# Sheet1.net
KiCad netlist of a schematic drawn in Altium Designer
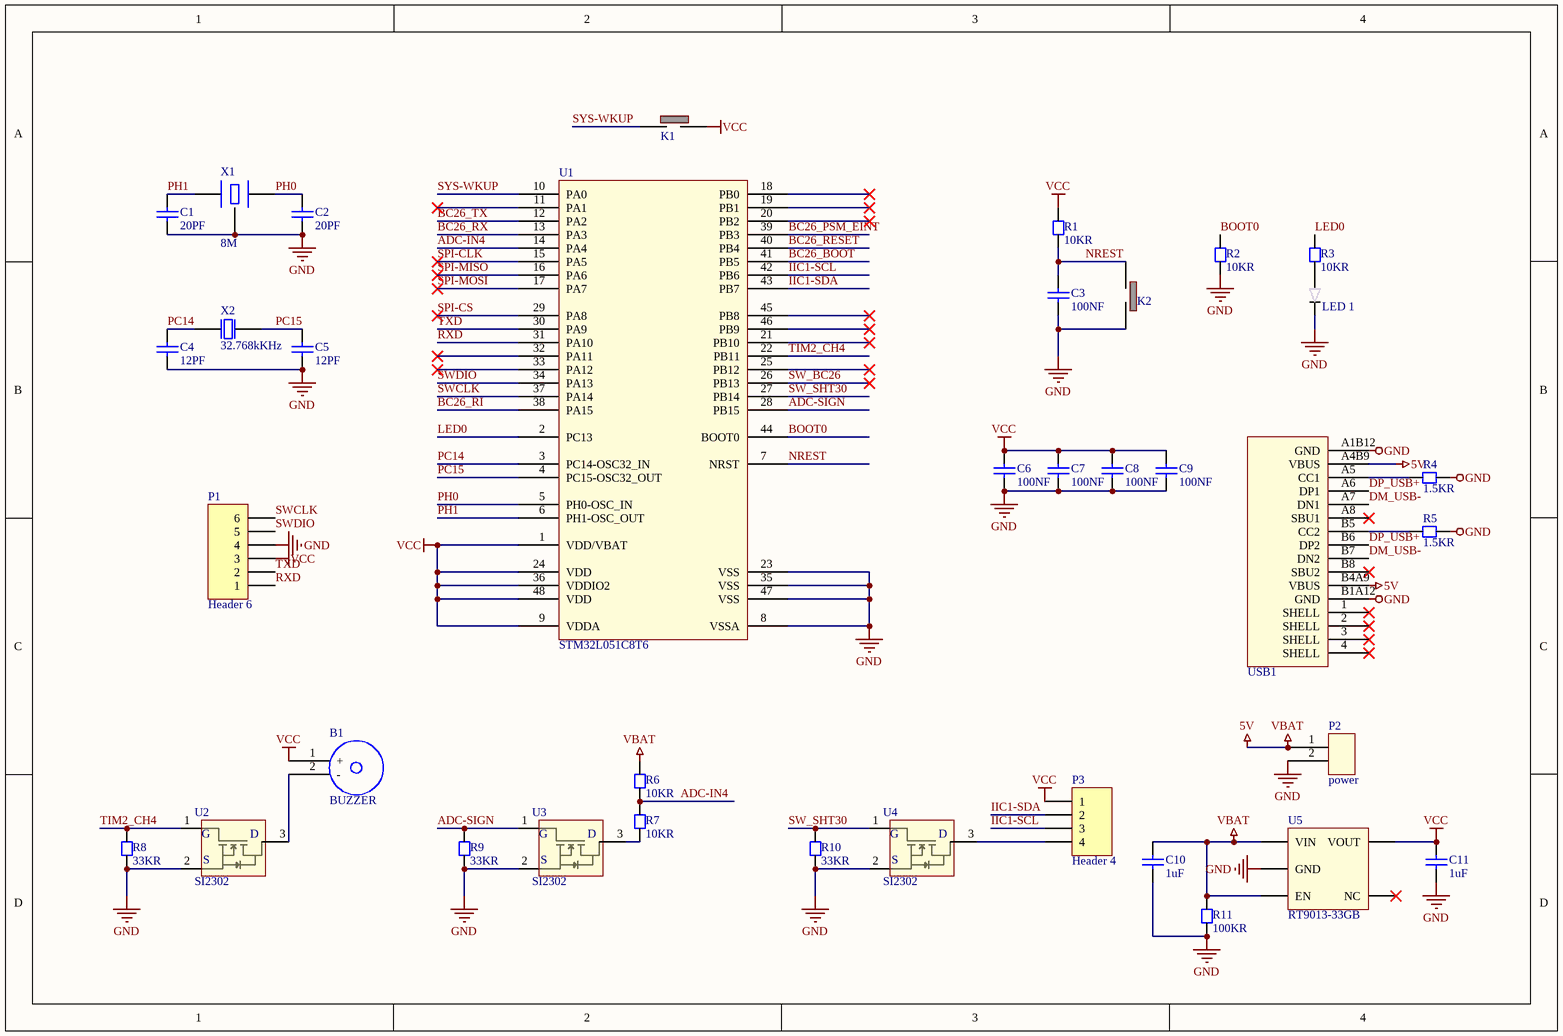
[diagram p0: Sheet1.SchDoc]

(export (version "E")
  (design (tool "Eeschema 10.0.6"))
  (components
    (comp (ref "B1")
      (value "BUZZER")
      (footprint "Buzzer")
      (description "蜂鸣器 0905 直径9毫米，高度5毫米")
      (libsource (lib "tianxiaohua_Schlib") (part "BUZZER"))
    )
    (comp (ref "C1")
      (value "20PF")
      (footprint "CC1608-0603")
      (description "贴片电容")
      (libsource (lib "tianxiaohua_Schlib") (part "Chip capacitor"))
    )
    (comp (ref "C2")
      (value "20PF")
      (footprint "CC1608-0603")
      (description "贴片电容")
      (libsource (lib "tianxiaohua_Schlib") (part "Chip capacitor"))
    )
    (comp (ref "C3")
      (value "100NF")
      (footprint "CC1608-0603")
      (description "贴片电容")
      (libsource (lib "tianxiaohua_Schlib") (part "Chip capacitor"))
    )
    (comp (ref "C4")
      (value "12PF")
      (footprint "CC1608-0603")
      (description "贴片电容")
      (libsource (lib "tianxiaohua_Schlib") (part "Chip capacitor"))
    )
    (comp (ref "C5")
      (value "12PF")
      (footprint "CC1608-0603")
      (description "贴片电容")
      (libsource (lib "tianxiaohua_Schlib") (part "Chip capacitor"))
    )
    (comp (ref "C6")
      (value "100NF")
      (footprint "CC1608-0603")
      (description "贴片电容")
      (libsource (lib "tianxiaohua_Schlib") (part "Chip capacitor"))
    )
    (comp (ref "C7")
      (value "100NF")
      (footprint "CC1608-0603")
      (description "贴片电容")
      (libsource (lib "tianxiaohua_Schlib") (part "Chip capacitor"))
    )
    (comp (ref "C8")
      (value "100NF")
      (footprint "CC1608-0603")
      (description "贴片电容")
      (libsource (lib "tianxiaohua_Schlib") (part "Chip capacitor"))
    )
    (comp (ref "C9")
      (value "100NF")
      (footprint "CC1608-0603")
      (description "贴片电容")
      (libsource (lib "tianxiaohua_Schlib") (part "Chip capacitor"))
    )
    (comp (ref "C10")
      (value "1uF")
      (footprint "CC1608-0603")
      (description "贴片电容")
      (libsource (lib "tianxiaohua_Schlib") (part "Chip capacitor"))
    )
    (comp (ref "C11")
      (value "1uF")
      (footprint "CC1608-0603")
      (description "贴片电容")
      (libsource (lib "tianxiaohua_Schlib") (part "Chip capacitor"))
    )
    (comp (ref "K1")
      (value "KEY 3*4")
      (footprint "KEY 3*4")
      (description "轻触开关按键")
      (libsource (lib "tianxiaohua_Schlib") (part "KEY 3*4"))
    )
    (comp (ref "K2")
      (value "KEY 3*4")
      (footprint "KEY 3*4")
      (description "轻触开关按键")
      (libsource (lib "") (part "KEY 3*4_1"))
    )
    (comp (ref "LED 1")
      (value "LED 0603")
      (footprint "LED 0603")
      (libsource (lib "tianxiaohua_Schlib") (part "LED 0603"))
    )
    (comp (ref "P1")
      (value "Header 6")
      (footprint "HDR1X6")
      (description "Header, 6-Pin")
      (fields (field (name "PUBLISHER") "Altium Limited"))
      (libsource (lib "EButterflyIntegratedLibrary") (part "Header 6"))
    )
    (comp (ref "P2")
      (value "power")
      (footprint "power-5V")
      (libsource (lib "tianxiaohua_Schlib") (part "power"))
    )
    (comp (ref "P3")
      (value "Header 4")
      (footprint "HX2.54-4")
      (description "Header, 4-Pin")
      (fields (field (name "PUBLISHER") "Altium Limited"))
      (libsource (lib "EButterflyIntegratedLibrary") (part "Header 4"))
    )
    (comp (ref "R1")
      (value "10KR")
      (footprint "CR1608-0603")
      (description "贴片电阻")
      (libsource (lib "tianxiaohua_Schlib") (part "Chip resistor"))
    )
    (comp (ref "R2")
      (value "10KR")
      (footprint "CR1608-0603")
      (description "贴片电阻")
      (libsource (lib "tianxiaohua_Schlib") (part "Chip resistor"))
    )
    (comp (ref "R3")
      (value "10KR")
      (footprint "CR1608-0603")
      (description "贴片电阻")
      (libsource (lib "tianxiaohua_Schlib") (part "Chip resistor"))
    )
    (comp (ref "R4")
      (value "1.5KR")
      (footprint "CR1608-0603")
      (description "贴片电阻")
      (libsource (lib "") (part "Chip resistor_2"))
    )
    (comp (ref "R5")
      (value "1.5KR")
      (footprint "CR1608-0603")
      (description "贴片电阻")
      (libsource (lib "") (part "Chip resistor_2"))
    )
    (comp (ref "R6")
      (value "10KR")
      (footprint "CR1608-0603")
      (description "贴片电阻")
      (libsource (lib "tianxiaohua_Schlib") (part "Chip resistor"))
    )
    (comp (ref "R7")
      (value "10KR")
      (footprint "CR1608-0603")
      (description "贴片电阻")
      (libsource (lib "tianxiaohua_Schlib") (part "Chip resistor"))
    )
    (comp (ref "R8")
      (value "33KR")
      (footprint "CR1608-0603")
      (description "贴片电阻")
      (libsource (lib "") (part "Chip resistor_1"))
    )
    (comp (ref "R9")
      (value "33KR")
      (footprint "CR1608-0603")
      (description "贴片电阻")
      (libsource (lib "") (part "Chip resistor_1"))
    )
    (comp (ref "R10")
      (value "33KR")
      (footprint "CR1608-0603")
      (description "贴片电阻")
      (libsource (lib "") (part "Chip resistor_1"))
    )
    (comp (ref "R11")
      (value "100KR")
      (footprint "CR1608-0603")
      (description "贴片电阻")
      (libsource (lib "tianxiaohua_Schlib") (part "Chip resistor"))
    )
    (comp (ref "U1")
      (value "STM32L051C8T6")
      (footprint "LQFP-48")
      (description "超低功耗单片机")
      (libsource (lib "tianxiaohua_Schlib") (part "STM32L051C8T6"))
    )
    (comp (ref "U2")
      (value "SI2302")
      (footprint "SOT-23")
      (description "NMOS场效应MOS管 SOT-23")
      (libsource (lib "tianxiaohua_Schlib") (part "SI2302"))
    )
    (comp (ref "U3")
      (value "SI2302")
      (footprint "SOT-23")
      (description "NMOS场效应MOS管 SOT-23")
      (libsource (lib "tianxiaohua_Schlib") (part "SI2302"))
    )
    (comp (ref "U4")
      (value "SI2302")
      (footprint "SOT-23")
      (description "NMOS场效应MOS管 SOT-23")
      (libsource (lib "tianxiaohua_Schlib") (part "SI2302"))
    )
    (comp (ref "U5")
      (value "RT9013-33GB")
      (footprint "SOT23-5")
      (description "LDO 2.2-5.2V IN 500Ma OUT SOT23-5")
      (libsource (lib "tianxiaohua_Schlib") (part "RT9013-33GB"))
    )
    (comp (ref "USB1")
      (value "Tpye-c 16P")
      (footprint "TYPE-C 16P")
      (description "16P 封装的TYPE -c接口 4固定插脚 双向")
      (libsource (lib "tianxiaohua_Schlib") (part "Tpye-c 16P"))
    )
    (comp (ref "X1")
      (value "8M")
      (footprint "XTAL-3225")
      (description "3225封装的晶振")
      (libsource (lib "tianxiaohua_Schlib") (part "XTAL 3225"))
    )
    (comp (ref "X2")
      (value "32.768kKHz")
      (footprint "XTAL-3215")
      (description "3215封装的时钟晶振")
      (libsource (lib "tianxiaohua_Schlib") (part "XTAL 3215 32.768kKHz"))
    )
  )
  (nets
    (net (code "1") (name "/ADC-IN4") (class "Default")
      (node (ref "R6") (pin "1") (pinfunction "1_1") (pintype "passive"))
      (node (ref "R7") (pin "2") (pinfunction "2_2") (pintype "passive"))
      (node (ref "U1") (pin "14") (pinfunction "PA4_14") (pintype "passive"))
    )
    (net (code "2") (name "/ADC-SIGN") (class "Default")
      (node (ref "R9") (pin "1") (pinfunction "1_1") (pintype "passive"))
      (node (ref "U1") (pin "28") (pinfunction "PB15_28") (pintype "passive"))
      (node (ref "U3") (pin "1") (pinfunction "GATE_1") (pintype "passive"))
    )
    (net (code "3") (name "/BC26_BOOT") (class "Default")
      (node (ref "U1") (pin "41") (pinfunction "PB5_41") (pintype "passive"))
    )
    (net (code "4") (name "/BC26_PSM_EINT") (class "Default")
      (node (ref "U1") (pin "39") (pinfunction "PB3_39") (pintype "passive"))
    )
    (net (code "5") (name "/BC26_RESET") (class "Default")
      (node (ref "U1") (pin "40") (pinfunction "PB4_40") (pintype "passive"))
    )
    (net (code "6") (name "/BC26_RI") (class "Default")
      (node (ref "U1") (pin "38") (pinfunction "PA15_38") (pintype "passive"))
    )
    (net (code "7") (name "/BC26_RX") (class "Default")
      (node (ref "U1") (pin "13") (pinfunction "PA3_13") (pintype "passive"))
    )
    (net (code "8") (name "/BC26_TX") (class "Default")
      (node (ref "U1") (pin "12") (pinfunction "PA2_12") (pintype "passive"))
    )
    (net (code "9") (name "/BOOT0") (class "Default")
      (node (ref "R2") (pin "2") (pinfunction "2_2") (pintype "passive"))
      (node (ref "U1") (pin "44") (pinfunction "BOOT0_44") (pintype "passive"))
    )
    (net (code "10") (name "/DM_USB-") (class "Default")
      (node (ref "USB1") (pin "A7") (pinfunction "DN1_A7") (pintype "power_in"))
      (node (ref "USB1") (pin "B7") (pinfunction "DN2_B7") (pintype "power_in"))
    )
    (net (code "11") (name "/DP_USB+") (class "Default")
      (node (ref "USB1") (pin "A6") (pinfunction "DP1_A6") (pintype "power_in"))
      (node (ref "USB1") (pin "B6") (pinfunction "DP2_B6") (pintype "power_in"))
    )
    (net (code "12") (name "/IIC1-SCL") (class "Default")
      (node (ref "P3") (pin "3") (pinfunction "3_3") (pintype "passive"))
      (node (ref "U1") (pin "42") (pinfunction "PB6_42") (pintype "passive"))
    )
    (net (code "13") (name "/IIC1-SDA") (class "Default")
      (node (ref "P3") (pin "2") (pinfunction "2_2") (pintype "passive"))
      (node (ref "U1") (pin "43") (pinfunction "PB7_43") (pintype "passive"))
    )
    (net (code "14") (name "/LED0") (class "Default")
      (node (ref "R3") (pin "2") (pinfunction "2_2") (pintype "passive"))
      (node (ref "U1") (pin "2") (pinfunction "PC13_2") (pintype "passive"))
    )
    (net (code "15") (name "/NREST") (class "Default")
      (node (ref "C3") (pin "2") (pinfunction "2_2") (pintype "passive"))
      (node (ref "K2") (pin "1") (pinfunction "1_1") (pintype "passive"))
      (node (ref "R1") (pin "1") (pinfunction "1_1") (pintype "passive"))
      (node (ref "U1") (pin "7") (pinfunction "NRST_7") (pintype "passive"))
    )
    (net (code "16") (name "/PC14") (class "Default")
      (node (ref "C4") (pin "2") (pinfunction "2_2") (pintype "passive"))
      (node (ref "U1") (pin "3") (pinfunction "PC14-OSC32_IN_3") (pintype "passive"))
      (node (ref "X2") (pin "1") (pinfunction "OSC1_1") (pintype "passive"))
    )
    (net (code "17") (name "/PC15") (class "Default")
      (node (ref "C5") (pin "2") (pinfunction "2_2") (pintype "passive"))
      (node (ref "U1") (pin "4") (pinfunction "PC15-OSC32_OUT_4") (pintype "passive"))
      (node (ref "X2") (pin "2") (pinfunction "OSC2_2") (pintype "passive"))
    )
    (net (code "18") (name "/PH0") (class "Default")
      (node (ref "C2") (pin "2") (pinfunction "2_2") (pintype "passive"))
      (node (ref "U1") (pin "5") (pinfunction "PH0-OSC_IN_5") (pintype "passive"))
      (node (ref "X1") (pin "3") (pinfunction "OSC2_3") (pintype "passive"))
    )
    (net (code "19") (name "/PH1") (class "Default")
      (node (ref "C1") (pin "2") (pinfunction "2_2") (pintype "passive"))
      (node (ref "U1") (pin "6") (pinfunction "PH1-OSC_OUT_6") (pintype "passive"))
      (node (ref "X1") (pin "1") (pinfunction "OSC1_1") (pintype "passive"))
    )
    (net (code "20") (name "/RXD") (class "Default")
      (node (ref "P1") (pin "1") (pinfunction "1_1") (pintype "passive"))
      (node (ref "U1") (pin "31") (pinfunction "PA10_31") (pintype "passive"))
    )
    (net (code "21") (name "/SPI-CLK") (class "Default")
      (node (ref "U1") (pin "15") (pinfunction "PA5_15") (pintype "passive+no_connect"))
    )
    (net (code "22") (name "/SPI-CS") (class "Default")
      (node (ref "U1") (pin "29") (pinfunction "PA8_29") (pintype "passive+no_connect"))
    )
    (net (code "23") (name "/SPI-MISO") (class "Default")
      (node (ref "U1") (pin "16") (pinfunction "PA6_16") (pintype "passive+no_connect"))
    )
    (net (code "24") (name "/SPI-MOSI") (class "Default")
      (node (ref "U1") (pin "17") (pinfunction "PA7_17") (pintype "passive+no_connect"))
    )
    (net (code "25") (name "/SWCLK") (class "Default")
      (node (ref "P1") (pin "6") (pinfunction "6_6") (pintype "passive"))
      (node (ref "U1") (pin "37") (pinfunction "PA14_37") (pintype "passive"))
    )
    (net (code "26") (name "/SWDIO") (class "Default")
      (node (ref "P1") (pin "5") (pinfunction "5_5") (pintype "passive"))
      (node (ref "U1") (pin "34") (pinfunction "PA13_34") (pintype "passive"))
    )
    (net (code "27") (name "/SW_BC26") (class "Default")
      (node (ref "U1") (pin "26") (pinfunction "PB13_26") (pintype "passive+no_connect"))
    )
    (net (code "28") (name "/SW_SHT30") (class "Default")
      (node (ref "R10") (pin "1") (pinfunction "1_1") (pintype "passive"))
      (node (ref "U1") (pin "27") (pinfunction "PB14_27") (pintype "passive"))
      (node (ref "U4") (pin "1") (pinfunction "GATE_1") (pintype "passive"))
    )
    (net (code "29") (name "/SYS-WKUP") (class "Default")
      (node (ref "K1") (pin "1") (pinfunction "1_1") (pintype "passive"))
      (node (ref "U1") (pin "10") (pinfunction "PA0_10") (pintype "passive"))
    )
    (net (code "30") (name "/TIM2_CH4") (class "Default")
      (node (ref "R8") (pin "1") (pinfunction "1_1") (pintype "passive"))
      (node (ref "U1") (pin "22") (pinfunction "PB11_22") (pintype "passive"))
      (node (ref "U2") (pin "1") (pinfunction "GATE_1") (pintype "passive"))
    )
    (net (code "31") (name "/TXD") (class "Default")
      (node (ref "P1") (pin "2") (pinfunction "2_2") (pintype "passive"))
      (node (ref "U1") (pin "30") (pinfunction "PA9_30") (pintype "passive"))
    )
    (net (code "32") (name "5V") (class "Default")
      (node (ref "C10") (pin "2") (pinfunction "2_2") (pintype "passive"))
      (node (ref "P2") (pin "1") (pinfunction "1_1") (pintype "passive"))
      (node (ref "R11") (pin "2") (pinfunction "2_2") (pintype "passive"))
      (node (ref "R6") (pin "2") (pinfunction "2_2") (pintype "passive"))
      (node (ref "U5") (pin "1") (pinfunction "VIN_1") (pintype "passive"))
      (node (ref "U5") (pin "3") (pinfunction "EN_3") (pintype "passive"))
      (node (ref "USB1") (pin "A4B9") (pinfunction "VBUS_A4B9") (pintype "power_in"))
      (node (ref "USB1") (pin "B4A9") (pinfunction "VBUS_B4A9") (pintype "power_in"))
    )
    (net (code "33") (name "GND") (class "Default")
      (node (ref "C1") (pin "1") (pinfunction "1_1") (pintype "passive"))
      (node (ref "C10") (pin "1") (pinfunction "1_1") (pintype "passive"))
      (node (ref "C11") (pin "1") (pinfunction "1_1") (pintype "passive"))
      (node (ref "C2") (pin "1") (pinfunction "1_1") (pintype "passive"))
      (node (ref "C3") (pin "1") (pinfunction "1_1") (pintype "passive"))
      (node (ref "C4") (pin "1") (pinfunction "1_1") (pintype "passive"))
      (node (ref "C5") (pin "1") (pinfunction "1_1") (pintype "passive"))
      (node (ref "C6") (pin "1") (pinfunction "1_1") (pintype "passive"))
      (node (ref "C7") (pin "1") (pinfunction "1_1") (pintype "passive"))
      (node (ref "C8") (pin "1") (pinfunction "1_1") (pintype "passive"))
      (node (ref "C9") (pin "1") (pinfunction "1_1") (pintype "passive"))
      (node (ref "K2") (pin "2") (pinfunction "2_2") (pintype "passive"))
      (node (ref "LED 1") (pin "2") (pinfunction "2_2") (pintype "passive"))
      (node (ref "P1") (pin "4") (pinfunction "4_4") (pintype "passive"))
      (node (ref "P2") (pin "2") (pinfunction "2_2") (pintype "passive"))
      (node (ref "R10") (pin "2") (pinfunction "2_2") (pintype "passive"))
      (node (ref "R11") (pin "1") (pinfunction "1_1") (pintype "passive"))
      (node (ref "R2") (pin "1") (pinfunction "1_1") (pintype "passive"))
      (node (ref "R4") (pin "1") (pinfunction "1_1") (pintype "passive"))
      (node (ref "R5") (pin "1") (pinfunction "1_1") (pintype "passive"))
      (node (ref "R8") (pin "2") (pinfunction "2_2") (pintype "passive"))
      (node (ref "R9") (pin "2") (pinfunction "2_2") (pintype "passive"))
      (node (ref "U1") (pin "23") (pinfunction "VSS_23") (pintype "passive"))
      (node (ref "U1") (pin "35") (pinfunction "VSS_35") (pintype "passive"))
      (node (ref "U1") (pin "47") (pinfunction "VSS_47") (pintype "passive"))
      (node (ref "U1") (pin "8") (pinfunction "VSSA_8") (pintype "passive"))
      (node (ref "U2") (pin "2") (pinfunction "SOURCE_2") (pintype "passive"))
      (node (ref "U3") (pin "2") (pinfunction "SOURCE_2") (pintype "passive"))
      (node (ref "U4") (pin "2") (pinfunction "SOURCE_2") (pintype "passive"))
      (node (ref "U5") (pin "2") (pinfunction "GND_2") (pintype "passive"))
      (node (ref "USB1") (pin "A1B12") (pinfunction "GND_A1B12") (pintype "power_in"))
      (node (ref "USB1") (pin "B1A12") (pinfunction "GND_B1A12") (pintype "power_in"))
      (node (ref "X1") (pin "2") (pinfunction "GND_2") (pintype "passive"))
    )
    (net (code "34") (name "Net-(B1--)") (class "Default")
      (node (ref "B1") (pin "2") (pinfunction "-_2") (pintype "passive"))
      (node (ref "U2") (pin "3") (pinfunction "DRAIN_3") (pintype "passive"))
    )
    (net (code "35") (name "Net-(LED 1-Pad1)") (class "Default")
      (node (ref "LED 1") (pin "1") (pinfunction "1_1") (pintype "passive"))
      (node (ref "R3") (pin "1") (pinfunction "1_1") (pintype "passive"))
    )
    (net (code "36") (name "Net-(U3-DRAIN)") (class "Default")
      (node (ref "R7") (pin "1") (pinfunction "1_1") (pintype "passive"))
      (node (ref "U3") (pin "3") (pinfunction "DRAIN_3") (pintype "passive"))
    )
    (net (code "37") (name "Net-(U4-DRAIN)") (class "Default")
      (node (ref "P3") (pin "4") (pinfunction "4_4") (pintype "passive"))
      (node (ref "U4") (pin "3") (pinfunction "DRAIN_3") (pintype "passive"))
    )
    (net (code "38") (name "Net-(USB1-CC1)") (class "Default")
      (node (ref "R4") (pin "2") (pinfunction "2_2") (pintype "passive"))
      (node (ref "USB1") (pin "A5") (pinfunction "CC1_A5") (pintype "power_in"))
    )
    (net (code "39") (name "Net-(USB1-CC2)") (class "Default")
      (node (ref "R5") (pin "2") (pinfunction "2_2") (pintype "passive"))
      (node (ref "USB1") (pin "B5") (pinfunction "CC2_B5") (pintype "power_in"))
    )
    (net (code "40") (name "VCC") (class "Default")
      (node (ref "B1") (pin "1") (pinfunction "+_1") (pintype "passive"))
      (node (ref "C11") (pin "2") (pinfunction "2_2") (pintype "passive"))
      (node (ref "C6") (pin "2") (pinfunction "2_2") (pintype "passive"))
      (node (ref "C7") (pin "2") (pinfunction "2_2") (pintype "passive"))
      (node (ref "C8") (pin "2") (pinfunction "2_2") (pintype "passive"))
      (node (ref "C9") (pin "2") (pinfunction "2_2") (pintype "passive"))
      (node (ref "K1") (pin "2") (pinfunction "2_2") (pintype "passive"))
      (node (ref "P1") (pin "3") (pinfunction "3_3") (pintype "passive"))
      (node (ref "P3") (pin "1") (pinfunction "1_1") (pintype "passive"))
      (node (ref "R1") (pin "2") (pinfunction "2_2") (pintype "passive"))
      (node (ref "U1") (pin "1") (pinfunction "VDD/VBAT_1") (pintype "passive"))
      (node (ref "U1") (pin "24") (pinfunction "VDD_24") (pintype "passive"))
      (node (ref "U1") (pin "36") (pinfunction "VDDIO2_36") (pintype "passive"))
      (node (ref "U1") (pin "48") (pinfunction "VDD_48") (pintype "passive"))
      (node (ref "U1") (pin "9") (pinfunction "VDDA_9") (pintype "passive"))
      (node (ref "U5") (pin "5") (pinfunction "VOUT_5") (pintype "passive"))
    )
    (net (code "41") (name "unconnected-(U1-PA1-Pad11)") (class "Default")
      (node (ref "U1") (pin "11") (pinfunction "PA1_11") (pintype "passive+no_connect"))
    )
    (net (code "42") (name "unconnected-(U1-PA11-Pad32)") (class "Default")
      (node (ref "U1") (pin "32") (pinfunction "PA11_32") (pintype "passive+no_connect"))
    )
    (net (code "43") (name "unconnected-(U1-PA12-Pad33)") (class "Default")
      (node (ref "U1") (pin "33") (pinfunction "PA12_33") (pintype "passive+no_connect"))
    )
    (net (code "44") (name "unconnected-(U1-PB0-Pad18)") (class "Default")
      (node (ref "U1") (pin "18") (pinfunction "PB0_18") (pintype "passive+no_connect"))
    )
    (net (code "45") (name "unconnected-(U1-PB1-Pad19)") (class "Default")
      (node (ref "U1") (pin "19") (pinfunction "PB1_19") (pintype "passive+no_connect"))
    )
    (net (code "46") (name "unconnected-(U1-PB2-Pad20)") (class "Default")
      (node (ref "U1") (pin "20") (pinfunction "PB2_20") (pintype "passive+no_connect"))
    )
    (net (code "47") (name "unconnected-(U1-PB8-Pad45)") (class "Default")
      (node (ref "U1") (pin "45") (pinfunction "PB8_45") (pintype "passive+no_connect"))
    )
    (net (code "48") (name "unconnected-(U1-PB9-Pad46)") (class "Default")
      (node (ref "U1") (pin "46") (pinfunction "PB9_46") (pintype "passive+no_connect"))
    )
    (net (code "49") (name "unconnected-(U1-PB10-Pad21)") (class "Default")
      (node (ref "U1") (pin "21") (pinfunction "PB10_21") (pintype "passive+no_connect"))
    )
    (net (code "50") (name "unconnected-(U1-PB12-Pad25)") (class "Default")
      (node (ref "U1") (pin "25") (pinfunction "PB12_25") (pintype "passive+no_connect"))
    )
    (net (code "51") (name "unconnected-(U5-NC-Pad4)") (class "Default")
      (node (ref "U5") (pin "4") (pinfunction "NC_4") (pintype "passive+no_connect"))
    )
    (net (code "52") (name "unconnected-(USB1-SBU1-PadA8)") (class "Default")
      (node (ref "USB1") (pin "A8") (pinfunction "SBU1_A8") (pintype "power_in+no_connect"))
    )
    (net (code "53") (name "unconnected-(USB1-SBU2-PadB8)") (class "Default")
      (node (ref "USB1") (pin "B8") (pinfunction "SBU2_B8") (pintype "power_in+no_connect"))
    )
    (net (code "54") (name "unconnected-(USB1-SHELL-Pad1)") (class "Default")
      (node (ref "USB1") (pin "1") (pinfunction "SHELL_1") (pintype "power_in+no_connect"))
    )
    (net (code "55") (name "unconnected-(USB1-SHELL-Pad2)") (class "Default")
      (node (ref "USB1") (pin "2") (pinfunction "SHELL_2") (pintype "power_in+no_connect"))
    )
    (net (code "56") (name "unconnected-(USB1-SHELL-Pad3)") (class "Default")
      (node (ref "USB1") (pin "3") (pinfunction "SHELL_3") (pintype "power_in+no_connect"))
    )
    (net (code "57") (name "unconnected-(USB1-SHELL-Pad4)") (class "Default")
      (node (ref "USB1") (pin "4") (pinfunction "SHELL_4") (pintype "power_in+no_connect"))
    )
  )
)
